# passiveXOR.net
KiCad netlist of a schematic drawn in EAGLE
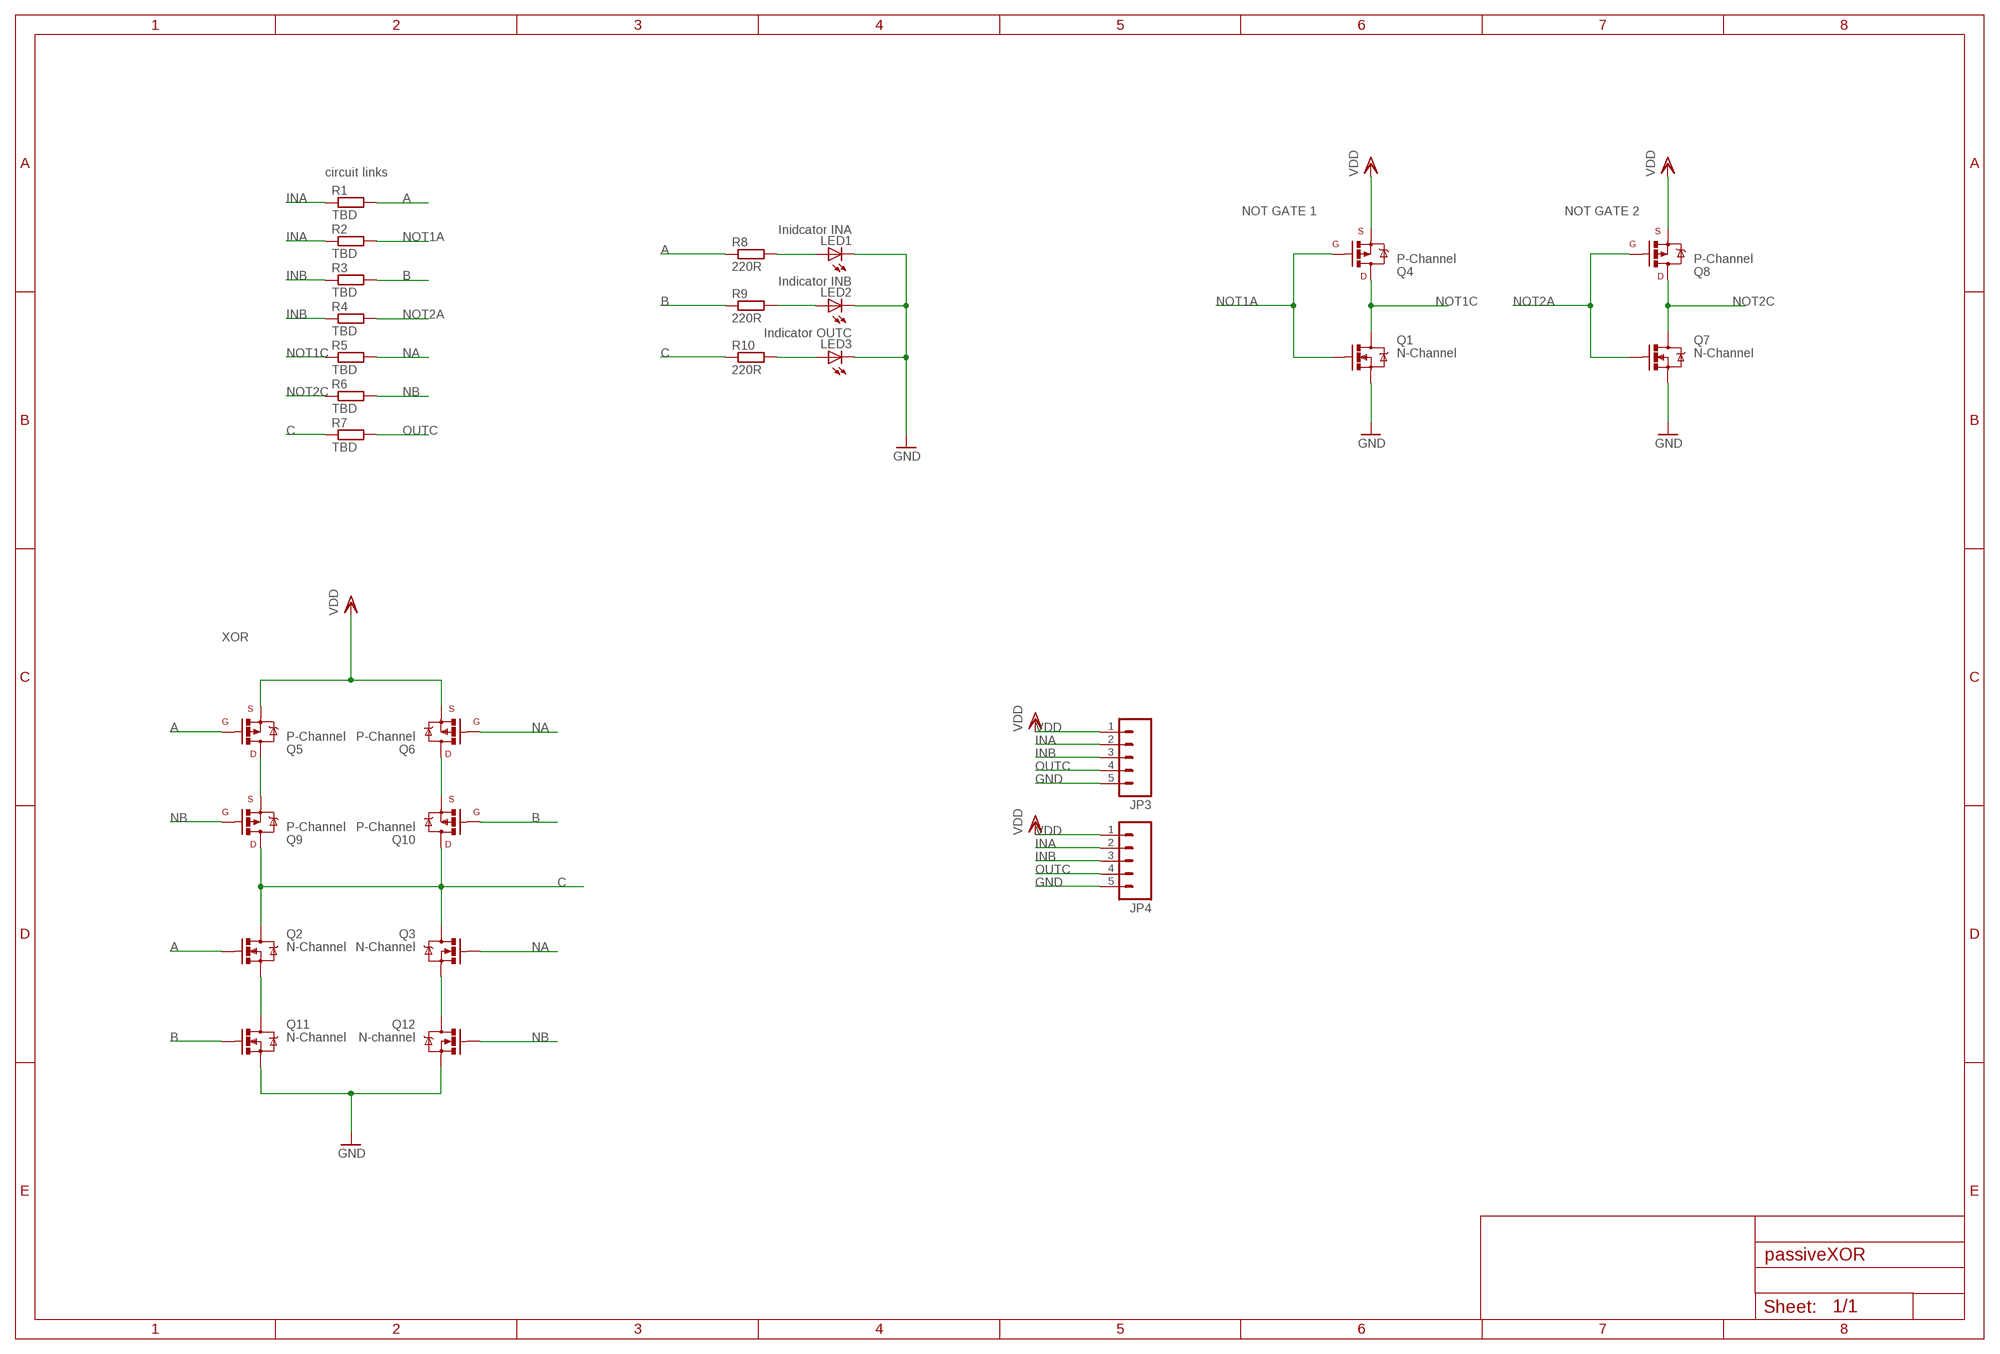
[diagram p0: schematic, sheet 1]

(export (version "E")
  (design (tool "Eeschema 10.0.6"))
  (components
    (comp (ref "JP3")
      (value "M05NO_SILK")
      (footprint "eagle-import:1X05_NO_SILK")
      (libsource (lib "eagle-import") (part "M05NO_SILK"))
    )
    (comp (ref "JP4")
      (value "M05NO_SILK")
      (footprint "eagle-import:1X05_NO_SILK")
      (libsource (lib "eagle-import") (part "M05NO_SILK"))
    )
    (comp (ref "LED1")
      (value "Inidcator INA")
      (footprint "eagle-import:CHIPLED_0805")
      (libsource (lib "eagle-import") (part "LEDCHIPLED_0805"))
    )
    (comp (ref "LED2")
      (value "Indicator INB")
      (footprint "eagle-import:CHIPLED_0805")
      (libsource (lib "eagle-import") (part "LEDCHIPLED_0805"))
    )
    (comp (ref "LED3")
      (value "Indicator OUTC")
      (footprint "eagle-import:CHIPLED_0805")
      (libsource (lib "eagle-import") (part "LEDCHIPLED_0805"))
    )
    (comp (ref "Q1")
      (value "N-Channel")
      (footprint "eagle-import:SOT23")
      (libsource (lib "eagle-import") (part "MOSFET-NCHANNEL"))
    )
    (comp (ref "Q2")
      (value "N-Channel")
      (footprint "eagle-import:SOT23")
      (libsource (lib "eagle-import") (part "MOSFET-NCHANNEL"))
    )
    (comp (ref "Q3")
      (value "N-Channel")
      (footprint "eagle-import:SOT23")
      (libsource (lib "eagle-import") (part "MOSFET-NCHANNEL"))
    )
    (comp (ref "Q4")
      (value "P-Channel")
      (footprint "eagle-import:SOT23")
      (libsource (lib "eagle-import") (part "MOSFET-PCHANNEL"))
    )
    (comp (ref "Q5")
      (value "P-Channel")
      (footprint "eagle-import:SOT23")
      (libsource (lib "eagle-import") (part "MOSFET-PCHANNEL"))
    )
    (comp (ref "Q6")
      (value "P-Channel")
      (footprint "eagle-import:SOT23")
      (libsource (lib "eagle-import") (part "MOSFET-PCHANNEL"))
    )
    (comp (ref "Q7")
      (value "N-Channel")
      (footprint "eagle-import:SOT23")
      (libsource (lib "eagle-import") (part "MOSFET-NCHANNEL"))
    )
    (comp (ref "Q8")
      (value "P-Channel")
      (footprint "eagle-import:SOT23")
      (libsource (lib "eagle-import") (part "MOSFET-PCHANNEL"))
    )
    (comp (ref "Q9")
      (value "P-Channel")
      (footprint "eagle-import:SOT23")
      (libsource (lib "eagle-import") (part "MOSFET-PCHANNEL"))
    )
    (comp (ref "Q10")
      (value "P-Channel")
      (footprint "eagle-import:SOT23")
      (libsource (lib "eagle-import") (part "MOSFET-PCHANNEL"))
    )
    (comp (ref "Q11")
      (value "N-Channel")
      (footprint "eagle-import:SOT23")
      (libsource (lib "eagle-import") (part "MOSFET-NCHANNEL"))
    )
    (comp (ref "Q12")
      (value "N-channel")
      (footprint "eagle-import:SOT23")
      (libsource (lib "eagle-import") (part "MOSFET-NCHANNEL"))
    )
    (comp (ref "R1")
      (value "TBD")
      (footprint "eagle-import:R0603")
      (libsource (lib "eagle-import") (part "R-EU_R0603"))
    )
    (comp (ref "R2")
      (value "TBD")
      (footprint "eagle-import:R0603")
      (libsource (lib "eagle-import") (part "R-EU_R0603"))
    )
    (comp (ref "R3")
      (value "TBD")
      (footprint "eagle-import:R0603")
      (libsource (lib "eagle-import") (part "R-EU_R0603"))
    )
    (comp (ref "R4")
      (value "TBD")
      (footprint "eagle-import:R0603")
      (libsource (lib "eagle-import") (part "R-EU_R0603"))
    )
    (comp (ref "R5")
      (value "TBD")
      (footprint "eagle-import:R0603")
      (libsource (lib "eagle-import") (part "R-EU_R0603"))
    )
    (comp (ref "R6")
      (value "TBD")
      (footprint "eagle-import:R0603")
      (libsource (lib "eagle-import") (part "R-EU_R0603"))
    )
    (comp (ref "R7")
      (value "TBD")
      (footprint "eagle-import:R0603")
      (libsource (lib "eagle-import") (part "R-EU_R0603"))
    )
    (comp (ref "R8")
      (value "220R")
      (footprint "eagle-import:R0603")
      (libsource (lib "eagle-import") (part "R-EU_R0603"))
    )
    (comp (ref "R9")
      (value "220R")
      (footprint "eagle-import:R0603")
      (libsource (lib "eagle-import") (part "R-EU_R0603"))
    )
    (comp (ref "R10")
      (value "220R")
      (footprint "eagle-import:R0603")
      (libsource (lib "eagle-import") (part "R-EU_R0603"))
    )
  )
  (nets
    (net (code "1") (name "/A") (class "Default")
      (node (ref "Q2") (pin "1") (pinfunction "G_1") (pintype "passive"))
      (node (ref "Q5") (pin "1") (pinfunction "G_1") (pintype "passive"))
      (node (ref "R1") (pin "2") (pinfunction "2_2") (pintype "passive"))
      (node (ref "R8") (pin "1") (pinfunction "1_1") (pintype "passive"))
    )
    (net (code "2") (name "/B") (class "Default")
      (node (ref "Q10") (pin "1") (pinfunction "G_1") (pintype "passive"))
      (node (ref "Q11") (pin "1") (pinfunction "G_1") (pintype "passive"))
      (node (ref "R3") (pin "2") (pinfunction "2_2") (pintype "passive"))
      (node (ref "R9") (pin "1") (pinfunction "1_1") (pintype "passive"))
    )
    (net (code "3") (name "/C") (class "Default")
      (node (ref "Q10") (pin "3") (pinfunction "D_3") (pintype "passive"))
      (node (ref "Q2") (pin "3") (pinfunction "D_3") (pintype "passive"))
      (node (ref "Q3") (pin "3") (pinfunction "D_3") (pintype "passive"))
      (node (ref "Q9") (pin "3") (pinfunction "D_3") (pintype "passive"))
      (node (ref "R10") (pin "1") (pinfunction "1_1") (pintype "passive"))
      (node (ref "R7") (pin "1") (pinfunction "1_1") (pintype "passive"))
    )
    (net (code "4") (name "/INA") (class "Default")
      (node (ref "JP3") (pin "2") (pinfunction "2_2") (pintype "passive"))
      (node (ref "JP4") (pin "2") (pinfunction "2_2") (pintype "passive"))
      (node (ref "R1") (pin "1") (pinfunction "1_1") (pintype "passive"))
      (node (ref "R2") (pin "1") (pinfunction "1_1") (pintype "passive"))
    )
    (net (code "5") (name "/INB") (class "Default")
      (node (ref "JP3") (pin "3") (pinfunction "3_3") (pintype "passive"))
      (node (ref "JP4") (pin "3") (pinfunction "3_3") (pintype "passive"))
      (node (ref "R3") (pin "1") (pinfunction "1_1") (pintype "passive"))
      (node (ref "R4") (pin "1") (pinfunction "1_1") (pintype "passive"))
    )
    (net (code "6") (name "/NA") (class "Default")
      (node (ref "Q3") (pin "1") (pinfunction "G_1") (pintype "passive"))
      (node (ref "Q6") (pin "1") (pinfunction "G_1") (pintype "passive"))
      (node (ref "R5") (pin "2") (pinfunction "2_2") (pintype "passive"))
    )
    (net (code "7") (name "/NB") (class "Default")
      (node (ref "Q12") (pin "1") (pinfunction "G_1") (pintype "passive"))
      (node (ref "Q9") (pin "1") (pinfunction "G_1") (pintype "passive"))
      (node (ref "R6") (pin "2") (pinfunction "2_2") (pintype "passive"))
    )
    (net (code "8") (name "/NOT1A") (class "Default")
      (node (ref "Q1") (pin "1") (pinfunction "G_1") (pintype "passive"))
      (node (ref "Q4") (pin "1") (pinfunction "G_1") (pintype "passive"))
      (node (ref "R2") (pin "2") (pinfunction "2_2") (pintype "passive"))
    )
    (net (code "9") (name "/NOT1C") (class "Default")
      (node (ref "Q1") (pin "3") (pinfunction "D_3") (pintype "passive"))
      (node (ref "Q4") (pin "3") (pinfunction "D_3") (pintype "passive"))
      (node (ref "R5") (pin "1") (pinfunction "1_1") (pintype "passive"))
    )
    (net (code "10") (name "/NOT2A") (class "Default")
      (node (ref "Q7") (pin "1") (pinfunction "G_1") (pintype "passive"))
      (node (ref "Q8") (pin "1") (pinfunction "G_1") (pintype "passive"))
      (node (ref "R4") (pin "2") (pinfunction "2_2") (pintype "passive"))
    )
    (net (code "11") (name "/NOT2C") (class "Default")
      (node (ref "Q7") (pin "3") (pinfunction "D_3") (pintype "passive"))
      (node (ref "Q8") (pin "3") (pinfunction "D_3") (pintype "passive"))
      (node (ref "R6") (pin "1") (pinfunction "1_1") (pintype "passive"))
    )
    (net (code "12") (name "/OUTC") (class "Default")
      (node (ref "JP3") (pin "4") (pinfunction "4_4") (pintype "passive"))
      (node (ref "JP4") (pin "4") (pinfunction "4_4") (pintype "passive"))
      (node (ref "R7") (pin "2") (pinfunction "2_2") (pintype "passive"))
    )
    (net (code "13") (name "GND") (class "Default")
      (node (ref "JP3") (pin "5") (pinfunction "5_5") (pintype "passive"))
      (node (ref "JP4") (pin "5") (pinfunction "5_5") (pintype "passive"))
      (node (ref "LED1") (pin "C") (pinfunction "C_C") (pintype "passive"))
      (node (ref "LED2") (pin "C") (pinfunction "C_C") (pintype "passive"))
      (node (ref "LED3") (pin "C") (pinfunction "C_C") (pintype "passive"))
      (node (ref "Q1") (pin "2") (pinfunction "S_2") (pintype "passive"))
      (node (ref "Q11") (pin "2") (pinfunction "S_2") (pintype "passive"))
      (node (ref "Q12") (pin "2") (pinfunction "S_2") (pintype "passive"))
      (node (ref "Q7") (pin "2") (pinfunction "S_2") (pintype "passive"))
    )
    (net (code "14") (name "Net-(LED1-PadA)") (class "Default")
      (node (ref "LED1") (pin "A") (pinfunction "A_A") (pintype "passive"))
      (node (ref "R8") (pin "2") (pinfunction "2_2") (pintype "passive"))
    )
    (net (code "15") (name "Net-(LED2-PadA)") (class "Default")
      (node (ref "LED2") (pin "A") (pinfunction "A_A") (pintype "passive"))
      (node (ref "R9") (pin "2") (pinfunction "2_2") (pintype "passive"))
    )
    (net (code "16") (name "Net-(LED3-PadA)") (class "Default")
      (node (ref "LED3") (pin "A") (pinfunction "A_A") (pintype "passive"))
      (node (ref "R10") (pin "2") (pinfunction "2_2") (pintype "passive"))
    )
    (net (code "17") (name "Net-(Q5-D)") (class "Default")
      (node (ref "Q5") (pin "3") (pinfunction "D_3") (pintype "passive"))
      (node (ref "Q9") (pin "2") (pinfunction "S_2") (pintype "passive"))
    )
    (net (code "18") (name "Net-(Q10-S)") (class "Default")
      (node (ref "Q10") (pin "2") (pinfunction "S_2") (pintype "passive"))
      (node (ref "Q6") (pin "3") (pinfunction "D_3") (pintype "passive"))
    )
    (net (code "19") (name "Net-(Q11-D)") (class "Default")
      (node (ref "Q11") (pin "3") (pinfunction "D_3") (pintype "passive"))
      (node (ref "Q2") (pin "2") (pinfunction "S_2") (pintype "passive"))
    )
    (net (code "20") (name "Net-(Q12-D)") (class "Default")
      (node (ref "Q12") (pin "3") (pinfunction "D_3") (pintype "passive"))
      (node (ref "Q3") (pin "2") (pinfunction "S_2") (pintype "passive"))
    )
    (net (code "21") (name "VDD") (class "Default")
      (node (ref "JP3") (pin "1") (pinfunction "1_1") (pintype "passive"))
      (node (ref "JP4") (pin "1") (pinfunction "1_1") (pintype "passive"))
      (node (ref "Q4") (pin "2") (pinfunction "S_2") (pintype "passive"))
      (node (ref "Q5") (pin "2") (pinfunction "S_2") (pintype "passive"))
      (node (ref "Q6") (pin "2") (pinfunction "S_2") (pintype "passive"))
      (node (ref "Q8") (pin "2") (pinfunction "S_2") (pintype "passive"))
    )
  )
)
